# plugV16-Add-Large-Cap-to-support-RELAY-s.net
KiCad netlist of a schematic drawn in EAGLE
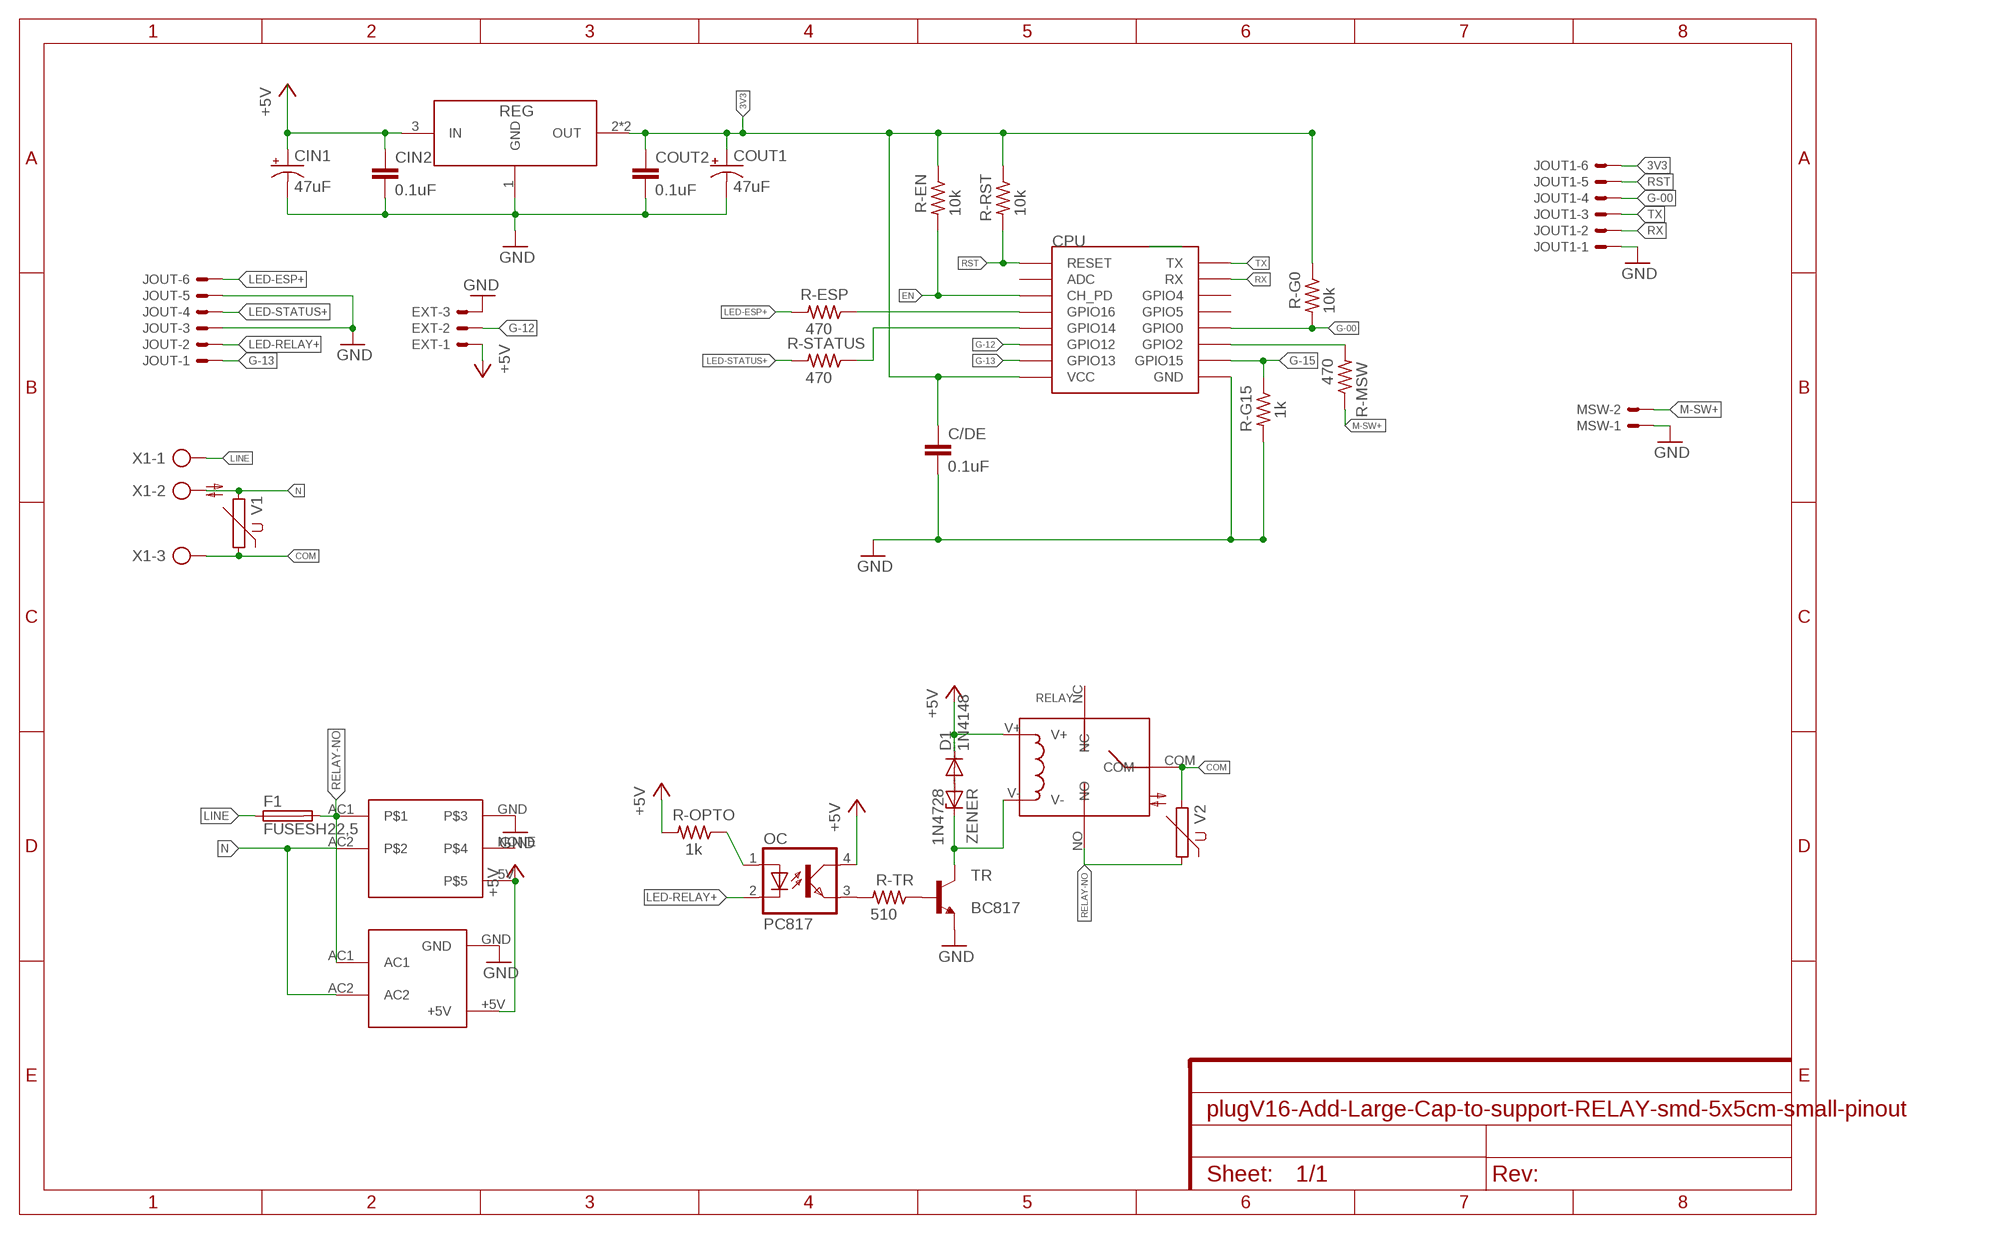
[diagram p0: schematic, sheet 1]

(export (version "E")
  (design (tool "Eeschema 10.0.6"))
  (components
    (comp (ref "C/DE")
      (value "0.1uF")
      (footprint "eagle-import:C0805")
      (libsource (lib "eagle-import") (part "C-EUC0805"))
    )
    (comp (ref "CIN1")
      (value "47uF")
      (footprint "eagle-import:E2,5-5")
      (libsource (lib "eagle-import") (part "CPOL-USE2.5-5"))
    )
    (comp (ref "CIN2")
      (value "0.1uF")
      (footprint "eagle-import:C0805")
      (libsource (lib "eagle-import") (part "C-EUC0805"))
    )
    (comp (ref "COUT1")
      (value "47uF")
      (footprint "eagle-import:E2,5-5")
      (libsource (lib "eagle-import") (part "CPOL-USE2.5-5"))
    )
    (comp (ref "COUT2")
      (value "0.1uF")
      (footprint "eagle-import:C0805")
      (libsource (lib "eagle-import") (part "C-EUC0805"))
    )
    (comp (ref "CPU")
      (value "ESP12SMD")
      (footprint "eagle-import:ESP12-SMD")
      (libsource (lib "eagle-import") (part "ESP12SMD"))
    )
    (comp (ref "D1")
      (value "1N4148")
      (footprint "eagle-import:DO35-7")
      (libsource (lib "eagle-import") (part "1N4148DO35-7"))
    )
    (comp (ref "EXT")
      (value "53048-03")
      (footprint "eagle-import:53048-03")
      (fields (field (name "MF") "WALDOM/MOLEX") (field (name "MPN") "53048-0310"))
      (libsource (lib "eagle-import") (part "53?-03048"))
    )
    (comp (ref "F1")
      (value "FUSESH22,5")
      (footprint "eagle-import:SH22,5")
      (libsource (lib "eagle-import") (part "FUSESH22,5"))
    )
    (comp (ref "HLK")
      (value "HLK-PM01")
      (footprint "eagle-import:HLK-PM01")
      (libsource (lib "eagle-import") (part "HLK-PM01"))
    )
    (comp (ref "JOUT")
      (value "53048-06")
      (footprint "eagle-import:53048-06")
      (fields (field (name "MF") "WALDOM/MOLEX") (field (name "MPN") "53048-0610"))
      (libsource (lib "eagle-import") (part "53?-06048"))
    )
    (comp (ref "JOUT1")
      (value "53048-06")
      (footprint "eagle-import:53048-06")
      (fields (field (name "MF") "WALDOM/MOLEX") (field (name "MPN") "53048-0610"))
      (libsource (lib "eagle-import") (part "53?-06048"))
    )
    (comp (ref "MSW")
      (value "53048-02")
      (footprint "eagle-import:53048-02")
      (fields (field (name "MF") "MOLEX") (field (name "MPN") "53048-0210"))
      (libsource (lib "eagle-import") (part "53?-02048"))
    )
    (comp (ref "OC")
      (value "PC817")
      (footprint "eagle-import:DIL04")
      (fields (field (name "MPN") "PC817X4J000F"))
      (libsource (lib "eagle-import") (part "PC817"))
    )
    (comp (ref "R-EN")
      (value "10k")
      (footprint "eagle-import:M0805")
      (libsource (lib "eagle-import") (part "R-US_M0805"))
    )
    (comp (ref "R-ESP")
      (value "470")
      (footprint "eagle-import:M0805")
      (libsource (lib "eagle-import") (part "R-US_M0805"))
    )
    (comp (ref "R-G0")
      (value "10k")
      (footprint "eagle-import:M0805")
      (libsource (lib "eagle-import") (part "R-US_M0805"))
    )
    (comp (ref "R-G15")
      (value "1k")
      (footprint "eagle-import:M0805")
      (libsource (lib "eagle-import") (part "R-US_M0805"))
    )
    (comp (ref "R-MSW")
      (value "470")
      (footprint "eagle-import:M0805")
      (libsource (lib "eagle-import") (part "R-US_M0805"))
    )
    (comp (ref "R-OPTO")
      (value "1k")
      (footprint "eagle-import:M0805")
      (libsource (lib "eagle-import") (part "R-US_M0805"))
    )
    (comp (ref "R-RST")
      (value "10k")
      (footprint "eagle-import:M0805")
      (libsource (lib "eagle-import") (part "R-US_M0805"))
    )
    (comp (ref "R-STATUS")
      (value "470")
      (footprint "eagle-import:M0805")
      (libsource (lib "eagle-import") (part "R-US_M0805"))
    )
    (comp (ref "R-TR")
      (value "510")
      (footprint "eagle-import:M0805")
      (libsource (lib "eagle-import") (part "R-US_M0805"))
    )
    (comp (ref "REG")
      (value "AMS1117-3.3")
      (footprint "eagle-import:SOT-223")
      (libsource (lib "eagle-import") (part "AMS1117-3.3"))
    )
    (comp (ref "RELAY")
      (value "RELAY-SONGLE")
      (footprint "eagle-import:RELAY-SONGLE")
      (libsource (lib "eagle-import") (part "RELAY-SONGLE"))
    )
    (comp (ref "TR")
      (value "BC817")
      (footprint "eagle-import:SOT23-BEC")
      (libsource (lib "eagle-import") (part "BC817SMD-16"))
    )
    (comp (ref "U$4")
      (value "POWERSUPPLY-5V-700MA")
      (footprint "eagle-import:POWERSUPPLY-5V-700MA")
      (libsource (lib "eagle-import") (part "POWERSUPPLY-5V-700MA"))
    )
    (comp (ref "V1")
      (value "S14K11")
      (footprint "eagle-import:S14K11")
      (libsource (lib "eagle-import") (part "S14K11"))
    )
    (comp (ref "V2")
      (value "S14K11")
      (footprint "eagle-import:S14K11")
      (libsource (lib "eagle-import") (part "S14K11"))
    )
    (comp (ref "X1")
      (value "AK300/3")
      (footprint "eagle-import:AK300_3")
      (libsource (lib "eagle-import") (part "AK300/3"))
    )
    (comp (ref "ZENER")
      (value "1N4728")
      (footprint "eagle-import:DO41Z10")
      (libsource (lib "eagle-import") (part "1N4728"))
    )
  )
  (nets
    (net (code "1") (name "+5V") (class "Default")
      (node (ref "CIN1") (pin "+") (pinfunction "+_+") (pintype "passive"))
      (node (ref "CIN2") (pin "1") (pinfunction "1_1") (pintype "passive"))
      (node (ref "D1") (pin "C") (pinfunction "C_C") (pintype "passive"))
      (node (ref "EXT") (pin "1") (pinfunction "S_1") (pintype "passive"))
      (node (ref "HLK") (pin "+5V") (pinfunction "+5V_+5V") (pintype "bidirectional"))
      (node (ref "OC") (pin "4") (pinfunction "COL_4") (pintype "passive"))
      (node (ref "R-OPTO") (pin "2") (pinfunction "2_2") (pintype "passive"))
      (node (ref "REG") (pin "3") (pinfunction "IN_3") (pintype "input"))
      (node (ref "RELAY") (pin "V+") (pinfunction "V+_V+") (pintype "bidirectional"))
      (node (ref "U$4") (pin "5V") (pinfunction "P$5_5V") (pintype "bidirectional"))
    )
    (net (code "2") (name "3V3") (class "Default")
      (node (ref "C/DE") (pin "1") (pinfunction "1_1") (pintype "passive"))
      (node (ref "COUT1") (pin "+") (pinfunction "+_+") (pintype "passive"))
      (node (ref "COUT2") (pin "1") (pinfunction "1_1") (pintype "passive"))
      (node (ref "CPU") (pin "VCC") (pinfunction "VCC_VCC") (pintype "bidirectional"))
      (node (ref "JOUT1") (pin "6") (pinfunction "S_6") (pintype "passive"))
      (node (ref "R-EN") (pin "1") (pinfunction "1_1") (pintype "passive"))
      (node (ref "R-G0") (pin "1") (pinfunction "1_1") (pintype "passive"))
      (node (ref "R-RST") (pin "1") (pinfunction "1_1") (pintype "passive"))
      (node (ref "REG") (pin "2") (pinfunction "OUT_2") (pintype "output"))
      (node (ref "REG") (pin "4") (pinfunction "OUT_4") (pintype "output"))
    )
    (net (code "3") (name "COM") (class "Default")
      (node (ref "RELAY") (pin "COM") (pinfunction "COM_COM") (pintype "bidirectional"))
      (node (ref "V1") (pin "1") (pinfunction "1_1") (pintype "passive"))
      (node (ref "V2") (pin "2") (pinfunction "2_2") (pintype "passive"))
      (node (ref "X1") (pin "3") (pinfunction "KL_3") (pintype "passive"))
    )
    (net (code "4") (name "EN") (class "Default")
      (node (ref "CPU") (pin "CH_PD") (pinfunction "CH_PD_CH_PD") (pintype "bidirectional"))
      (node (ref "R-EN") (pin "2") (pinfunction "2_2") (pintype "passive"))
    )
    (net (code "5") (name "G-00") (class "Default")
      (node (ref "CPU") (pin "GPIO0") (pinfunction "GPIO0_GPIO0") (pintype "bidirectional"))
      (node (ref "JOUT1") (pin "4") (pinfunction "S_4") (pintype "passive"))
      (node (ref "R-G0") (pin "2") (pinfunction "2_2") (pintype "passive"))
    )
    (net (code "6") (name "G-12") (class "Default")
      (node (ref "CPU") (pin "GPIO12") (pinfunction "GPIO12_GPIO12") (pintype "bidirectional"))
      (node (ref "EXT") (pin "2") (pinfunction "S_2") (pintype "passive"))
    )
    (net (code "7") (name "G-13") (class "Default")
      (node (ref "CPU") (pin "GPIO13") (pinfunction "GPIO13_GPIO13") (pintype "bidirectional"))
      (node (ref "JOUT") (pin "1") (pinfunction "S_1") (pintype "passive"))
    )
    (net (code "8") (name "G-15") (class "Default")
      (node (ref "CPU") (pin "GPIO15") (pinfunction "GPIO15_GPIO15") (pintype "bidirectional"))
      (node (ref "R-G15") (pin "1") (pinfunction "1_1") (pintype "passive"))
    )
    (net (code "9") (name "GND") (class "Default")
      (node (ref "C/DE") (pin "2") (pinfunction "2_2") (pintype "passive"))
      (node (ref "CIN1") (pin "-") (pinfunction "-_-") (pintype "passive"))
      (node (ref "CIN2") (pin "2") (pinfunction "2_2") (pintype "passive"))
      (node (ref "COUT1") (pin "-") (pinfunction "-_-") (pintype "passive"))
      (node (ref "COUT2") (pin "2") (pinfunction "2_2") (pintype "passive"))
      (node (ref "CPU") (pin "GND") (pinfunction "GND_GND") (pintype "bidirectional"))
      (node (ref "EXT") (pin "3") (pinfunction "S_3") (pintype "passive"))
      (node (ref "HLK") (pin "GND") (pinfunction "GND_GND") (pintype "bidirectional"))
      (node (ref "JOUT") (pin "3") (pinfunction "S_3") (pintype "passive"))
      (node (ref "JOUT") (pin "5") (pinfunction "S_5") (pintype "passive"))
      (node (ref "JOUT1") (pin "1") (pinfunction "S_1") (pintype "passive"))
      (node (ref "MSW") (pin "1") (pinfunction "S_1") (pintype "passive"))
      (node (ref "R-G15") (pin "2") (pinfunction "2_2") (pintype "passive"))
      (node (ref "REG") (pin "1") (pinfunction "GND_1") (pintype "passive"))
      (node (ref "TR") (pin "E") (pinfunction "E_E") (pintype "passive"))
      (node (ref "U$4") (pin "GND") (pinfunction "P$3_GND") (pintype "bidirectional"))
    )
    (net (code "10") (name "LED-ESP+") (class "Default")
      (node (ref "JOUT") (pin "6") (pinfunction "S_6") (pintype "passive"))
      (node (ref "R-ESP") (pin "2") (pinfunction "2_2") (pintype "passive"))
    )
    (net (code "11") (name "LED-RELAY+") (class "Default")
      (node (ref "JOUT") (pin "2") (pinfunction "S_2") (pintype "passive"))
      (node (ref "OC") (pin "2") (pinfunction "C_2") (pintype "passive"))
    )
    (net (code "12") (name "LED-STATUS+") (class "Default")
      (node (ref "JOUT") (pin "4") (pinfunction "S_4") (pintype "passive"))
      (node (ref "R-STATUS") (pin "2") (pinfunction "2_2") (pintype "passive"))
    )
    (net (code "13") (name "LINE") (class "Default")
      (node (ref "F1") (pin "1") (pinfunction "1_1") (pintype "passive"))
      (node (ref "X1") (pin "1") (pinfunction "KL_1") (pintype "passive"))
    )
    (net (code "14") (name "M-SW+") (class "Default")
      (node (ref "MSW") (pin "2") (pinfunction "S_2") (pintype "passive"))
      (node (ref "R-MSW") (pin "1") (pinfunction "1_1") (pintype "passive"))
    )
    (net (code "15") (name "N") (class "Default")
      (node (ref "HLK") (pin "AC2") (pinfunction "AC2_AC2") (pintype "bidirectional"))
      (node (ref "U$4") (pin "AC2") (pinfunction "P$2_AC2") (pintype "bidirectional"))
      (node (ref "V1") (pin "2") (pinfunction "2_2") (pintype "passive"))
      (node (ref "X1") (pin "2") (pinfunction "KL_2") (pintype "passive"))
    )
    (net (code "16") (name "Net-(CPU-PadGPIO2)") (class "Default")
      (node (ref "CPU") (pin "GPIO2") (pinfunction "GPIO2_GPIO2") (pintype "bidirectional"))
      (node (ref "R-MSW") (pin "2") (pinfunction "2_2") (pintype "passive"))
    )
    (net (code "17") (name "Net-(CPU-PadGPIO14)") (class "Default")
      (node (ref "CPU") (pin "GPIO14") (pinfunction "GPIO14_GPIO14") (pintype "bidirectional"))
      (node (ref "R-STATUS") (pin "1") (pinfunction "1_1") (pintype "passive"))
    )
    (net (code "18") (name "Net-(CPU-PadGPIO16)") (class "Default")
      (node (ref "CPU") (pin "GPIO16") (pinfunction "GPIO16_GPIO16") (pintype "bidirectional"))
      (node (ref "R-ESP") (pin "1") (pinfunction "1_1") (pintype "passive"))
    )
    (net (code "19") (name "Net-(D1-PadA)") (class "Default")
      (node (ref "D1") (pin "A") (pinfunction "A_A") (pintype "passive"))
      (node (ref "ZENER") (pin "A") (pinfunction "A_A") (pintype "passive"))
    )
    (net (code "20") (name "Net-(OC-A)") (class "Default")
      (node (ref "OC") (pin "1") (pinfunction "A_1") (pintype "passive"))
      (node (ref "R-OPTO") (pin "1") (pinfunction "1_1") (pintype "passive"))
    )
    (net (code "21") (name "Net-(OC-EMIT)") (class "Default")
      (node (ref "OC") (pin "3") (pinfunction "EMIT_3") (pintype "passive"))
      (node (ref "R-TR") (pin "2") (pinfunction "2_2") (pintype "passive"))
    )
    (net (code "22") (name "Net-(R-TR-Pad1)") (class "Default")
      (node (ref "R-TR") (pin "1") (pinfunction "1_1") (pintype "passive"))
      (node (ref "TR") (pin "B") (pinfunction "B_B") (pintype "passive"))
    )
    (net (code "23") (name "Net-(RELAY-PadV-)") (class "Default")
      (node (ref "RELAY") (pin "V-") (pinfunction "V-_V-") (pintype "bidirectional"))
      (node (ref "TR") (pin "C") (pinfunction "C_C") (pintype "passive"))
      (node (ref "ZENER") (pin "C") (pinfunction "C_C") (pintype "passive"))
    )
    (net (code "24") (name "RELAY-NO") (class "Default")
      (node (ref "F1") (pin "2") (pinfunction "2_2") (pintype "passive"))
      (node (ref "HLK") (pin "AC1") (pinfunction "AC1_AC1") (pintype "bidirectional"))
      (node (ref "RELAY") (pin "NO") (pinfunction "NO_NO") (pintype "bidirectional"))
      (node (ref "U$4") (pin "AC1") (pinfunction "P$1_AC1") (pintype "bidirectional"))
      (node (ref "V2") (pin "1") (pinfunction "1_1") (pintype "passive"))
    )
    (net (code "25") (name "RST") (class "Default")
      (node (ref "CPU") (pin "RESET") (pinfunction "RESET_RESET") (pintype "bidirectional"))
      (node (ref "JOUT1") (pin "5") (pinfunction "S_5") (pintype "passive"))
      (node (ref "R-RST") (pin "2") (pinfunction "2_2") (pintype "passive"))
    )
    (net (code "26") (name "RX") (class "Default")
      (node (ref "CPU") (pin "RXD0") (pinfunction "RX_RXD0") (pintype "bidirectional"))
      (node (ref "JOUT1") (pin "2") (pinfunction "S_2") (pintype "passive"))
    )
    (net (code "27") (name "TX") (class "Default")
      (node (ref "CPU") (pin "TXD0") (pinfunction "TX_TXD0") (pintype "bidirectional"))
      (node (ref "JOUT1") (pin "3") (pinfunction "S_3") (pintype "passive"))
    )
    (net (code "28") (name "unconnected-(CPU-PadADC)") (class "Default")
      (node (ref "CPU") (pin "ADC") (pinfunction "ADC_ADC") (pintype "bidirectional"))
    )
    (net (code "29") (name "unconnected-(CPU-PadGPIO4)") (class "Default")
      (node (ref "CPU") (pin "GPIO4") (pinfunction "GPIO4_GPIO4") (pintype "bidirectional"))
    )
    (net (code "30") (name "unconnected-(CPU-PadGPIO5)") (class "Default")
      (node (ref "CPU") (pin "GPIO5") (pinfunction "GPIO5_GPIO5") (pintype "bidirectional"))
    )
    (net (code "31") (name "unconnected-(RELAY-PadNC)") (class "Default")
      (node (ref "RELAY") (pin "NC") (pinfunction "NC_NC") (pintype "bidirectional"))
    )
    (net (code "32") (name "unconnected-(U$4-P$4-PadNONE)") (class "Default")
      (node (ref "U$4") (pin "NONE") (pinfunction "P$4_NONE") (pintype "bidirectional"))
    )
  )
)
